# Plan1.net
KiCad netlist of a schematic drawn in EAGLE
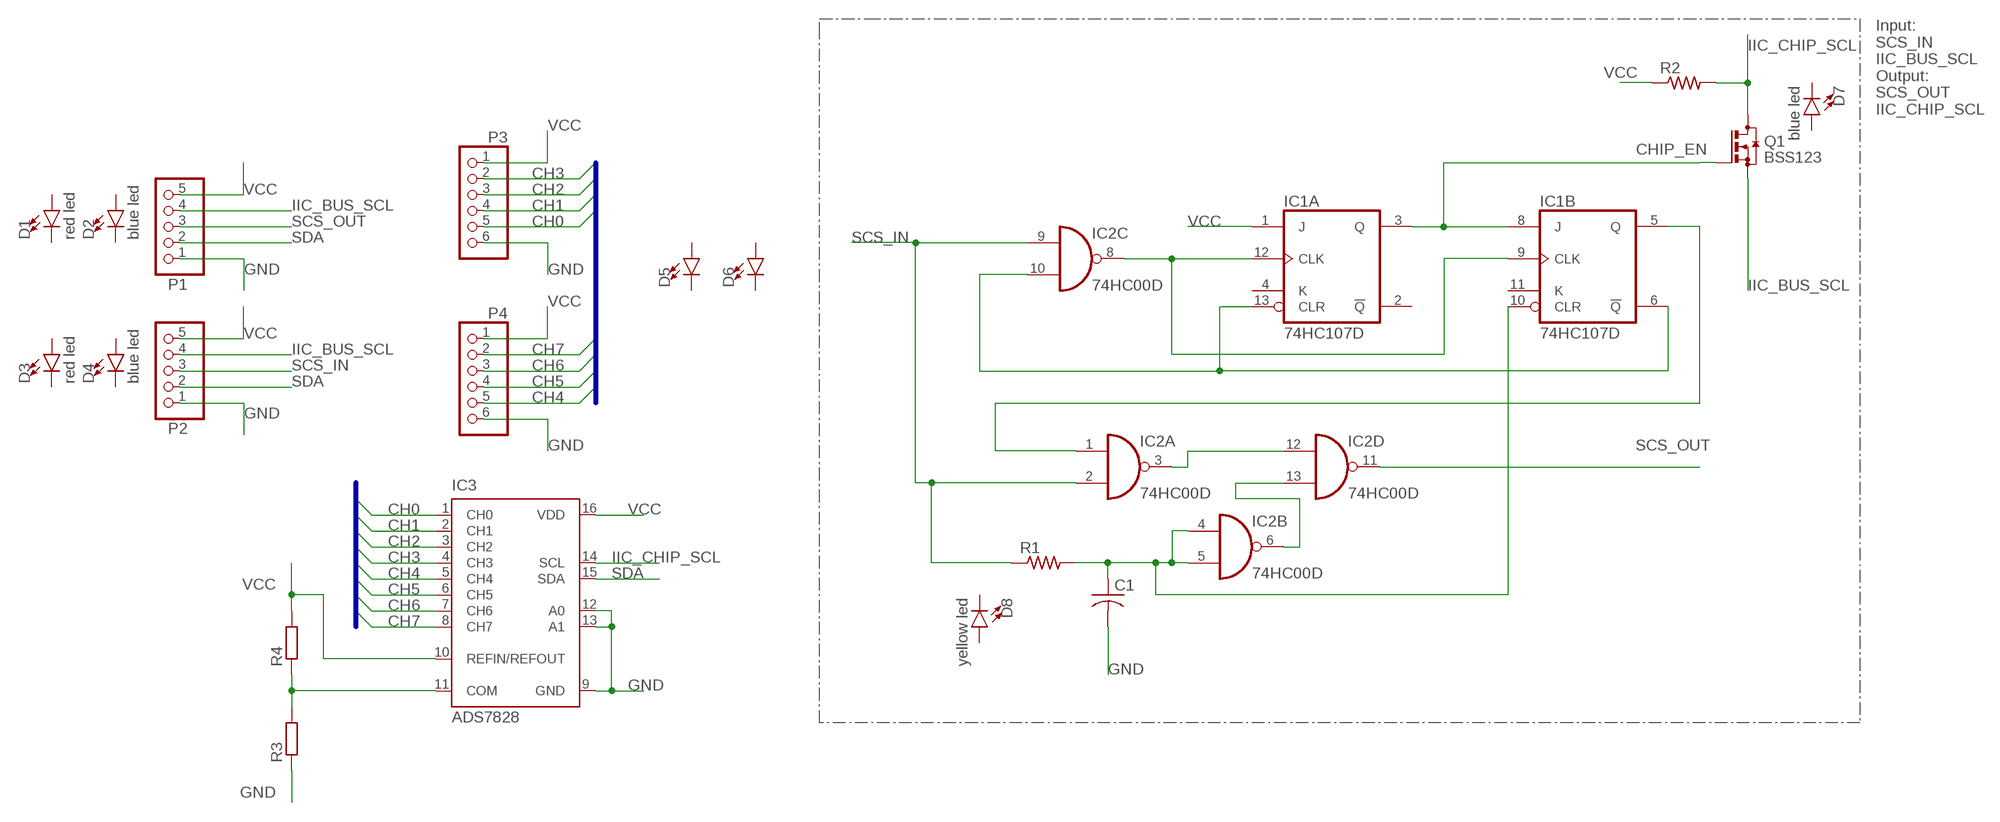
[diagram p0: schematic, sheet 1]

(export (version "E")
  (design (tool "Eeschema 10.0.6"))
  (components
    (comp (ref "C1")
      (value "C-USC1206")
      (footprint "eagle-import:C1206")
      (libsource (lib "eagle-import") (part "C-USC1206"))
    )
    (comp (ref "D1")
      (value "red led")
      (footprint "eagle-import:LED-0603")
      (libsource (lib "eagle-import") (part "LED0603"))
    )
    (comp (ref "D2")
      (value "blue led")
      (footprint "eagle-import:LED-0603")
      (libsource (lib "eagle-import") (part "LED0603"))
    )
    (comp (ref "D3")
      (value "red led")
      (footprint "eagle-import:LED-0603")
      (libsource (lib "eagle-import") (part "LED0603"))
    )
    (comp (ref "D4")
      (value "blue led")
      (footprint "eagle-import:LED-0603")
      (libsource (lib "eagle-import") (part "LED0603"))
    )
    (comp (ref "D5")
      (value "LED0603")
      (footprint "eagle-import:LED-0603")
      (libsource (lib "eagle-import") (part "LED0603"))
    )
    (comp (ref "D6")
      (value "LED0603")
      (footprint "eagle-import:LED-0603")
      (libsource (lib "eagle-import") (part "LED0603"))
    )
    (comp (ref "D7")
      (value "blue led")
      (footprint "eagle-import:LED-0603")
      (libsource (lib "eagle-import") (part "LED0603"))
    )
    (comp (ref "D8")
      (value "yellow led")
      (footprint "eagle-import:LED-0603")
      (libsource (lib "eagle-import") (part "LED0603"))
    )
    (comp (ref "IC1")
      (value "74HC107D")
      (footprint "eagle-import:SO14")
      (libsource (lib "eagle-import") (part "74107DHC"))
    )
    (comp (ref "IC2")
      (value "74HC00D")
      (footprint "eagle-import:SO14")
      (libsource (lib "eagle-import") (part "7400DHC"))
    )
    (comp (ref "IC3")
      (value "ADS7828")
      (footprint "eagle-import:TSSOP16-PW")
      (fields (field (name "MF") "TEXAS INSTRUMENTS") (field (name "MPN") "ADS7828E/250"))
      (libsource (lib "eagle-import") (part "ADS7828"))
    )
    (comp (ref "P1")
      (value "105313-05")
      (footprint "eagle-import:105313-__05")
      (fields (field (name "MF") "Molex"))
      (libsource (lib "eagle-import") (part "105313-05"))
    )
    (comp (ref "P2")
      (value "105313-05")
      (footprint "eagle-import:105313-__05")
      (fields (field (name "MF") "Molex"))
      (libsource (lib "eagle-import") (part "105313-05"))
    )
    (comp (ref "P3")
      (value "105313-06")
      (footprint "eagle-import:105313-__06")
      (fields (field (name "MF") "Molex"))
      (libsource (lib "eagle-import") (part "105313-06"))
    )
    (comp (ref "P4")
      (value "105313-06")
      (footprint "eagle-import:105313-__06")
      (fields (field (name "MF") "Molex"))
      (libsource (lib "eagle-import") (part "105313-06"))
    )
    (comp (ref "Q1")
      (value "BSS123")
      (footprint "eagle-import:SOT23")
      (libsource (lib "eagle-import") (part "BSS123"))
    )
    (comp (ref "R1")
      (value "R-US_R1206")
      (footprint "eagle-import:R1206")
      (libsource (lib "eagle-import") (part "R-US_R1206"))
    )
    (comp (ref "R2")
      (value "R-US_R1206")
      (footprint "eagle-import:R1206")
      (libsource (lib "eagle-import") (part "R-US_R1206"))
    )
    (comp (ref "R3")
      (value "R-EU_R2012")
      (footprint "eagle-import:R2012")
      (libsource (lib "eagle-import") (part "R-EU_R2012"))
    )
    (comp (ref "R4")
      (value "R-EU_R2012")
      (footprint "eagle-import:R2012")
      (libsource (lib "eagle-import") (part "R-EU_R2012"))
    )
  )
  (nets
    (net (code "10") (name "CH0") (class "Default")
      (node (ref "IC3") (pin "1") (pinfunction "CH0_1") (pintype "input"))
      (node (ref "P3") (pin "5") (pinfunction "5_5") (pintype "passive"))
    )
    (net (code "11") (name "CH1") (class "Default")
      (node (ref "IC3") (pin "2") (pinfunction "CH1_2") (pintype "input"))
      (node (ref "P3") (pin "4") (pinfunction "4_4") (pintype "passive"))
    )
    (net (code "12") (name "CH2") (class "Default")
      (node (ref "IC3") (pin "3") (pinfunction "CH2_3") (pintype "input"))
      (node (ref "P3") (pin "3") (pinfunction "3_3") (pintype "passive"))
    )
    (net (code "13") (name "CH3") (class "Default")
      (node (ref "IC3") (pin "4") (pinfunction "CH3_4") (pintype "input"))
      (node (ref "P3") (pin "2") (pinfunction "2_2") (pintype "passive"))
    )
    (net (code "14") (name "CH4") (class "Default")
      (node (ref "IC3") (pin "5") (pinfunction "CH4_5") (pintype "input"))
      (node (ref "P4") (pin "5") (pinfunction "5_5") (pintype "passive"))
    )
    (net (code "15") (name "CH5") (class "Default")
      (node (ref "IC3") (pin "6") (pinfunction "CH5_6") (pintype "input"))
      (node (ref "P4") (pin "4") (pinfunction "4_4") (pintype "passive"))
    )
    (net (code "16") (name "CH6") (class "Default")
      (node (ref "IC3") (pin "7") (pinfunction "CH6_7") (pintype "input"))
      (node (ref "P4") (pin "3") (pinfunction "3_3") (pintype "passive"))
    )
    (net (code "17") (name "CH7") (class "Default")
      (node (ref "IC3") (pin "8") (pinfunction "CH7_8") (pintype "input"))
      (node (ref "P4") (pin "2") (pinfunction "2_2") (pintype "passive"))
    )
    (net (code "18") (name "CHIP_EN") (class "Default")
      (node (ref "IC1") (pin "3") (pinfunction "Q_3") (pintype "output"))
      (node (ref "IC1") (pin "8") (pinfunction "J_8") (pintype "input"))
      (node (ref "Q1") (pin "1") (pinfunction "G_1") (pintype "passive"))
    )
    (net (code "19") (name "GND") (class "Default")
      (node (ref "C1") (pin "2") (pinfunction "2_2") (pintype "passive"))
      (node (ref "IC3") (pin "12") (pinfunction "A0_12") (pintype "input"))
      (node (ref "IC3") (pin "13") (pinfunction "A1_13") (pintype "input"))
      (node (ref "IC3") (pin "9") (pinfunction "GND_9") (pintype "power_in"))
      (node (ref "P1") (pin "1") (pinfunction "1_1") (pintype "passive"))
      (node (ref "P2") (pin "1") (pinfunction "1_1") (pintype "passive"))
      (node (ref "P3") (pin "6") (pinfunction "6_6") (pintype "passive"))
      (node (ref "P4") (pin "6") (pinfunction "6_6") (pintype "passive"))
      (node (ref "R3") (pin "1") (pinfunction "1_1") (pintype "passive"))
    )
    (net (code "20") (name "IIC_BUS_SCL") (class "Default")
      (node (ref "P1") (pin "4") (pinfunction "4_4") (pintype "passive"))
      (node (ref "P2") (pin "4") (pinfunction "4_4") (pintype "passive"))
      (node (ref "Q1") (pin "2") (pinfunction "S_2") (pintype "passive"))
    )
    (net (code "21") (name "IIC_CHIP_SCL") (class "Default")
      (node (ref "IC3") (pin "14") (pinfunction "SCL_14") (pintype "input"))
      (node (ref "Q1") (pin "3") (pinfunction "D_3") (pintype "passive"))
      (node (ref "R2") (pin "2") (pinfunction "2_2") (pintype "passive"))
    )
    (net (code "22") (name "Net-(IC1A-CLK)") (class "Default")
      (node (ref "IC1") (pin "12") (pinfunction "CLK_12") (pintype "input"))
      (node (ref "IC1") (pin "9") (pinfunction "CLK_9") (pintype "input"))
      (node (ref "IC2") (pin "8") (pinfunction "O_8") (pintype "output"))
    )
    (net (code "23") (name "Net-(IC1A-CLR)") (class "Default")
      (node (ref "IC1") (pin "13") (pinfunction "CLR_13") (pintype "input"))
      (node (ref "IC1") (pin "6") (pinfunction "~{Q}_6") (pintype "output"))
      (node (ref "IC2") (pin "10") (pinfunction "I1_10") (pintype "input"))
    )
    (net (code "24") (name "Net-(IC1B-CLR)") (class "Default")
      (node (ref "C1") (pin "1") (pinfunction "1_1") (pintype "passive"))
      (node (ref "IC1") (pin "10") (pinfunction "CLR_10") (pintype "input"))
      (node (ref "IC2") (pin "4") (pinfunction "I0_4") (pintype "input"))
      (node (ref "IC2") (pin "5") (pinfunction "I1_5") (pintype "input"))
      (node (ref "R1") (pin "2") (pinfunction "2_2") (pintype "passive"))
    )
    (net (code "25") (name "Net-(IC1B-Q)") (class "Default")
      (node (ref "IC1") (pin "5") (pinfunction "Q_5") (pintype "output"))
      (node (ref "IC2") (pin "1") (pinfunction "I0_1") (pintype "input"))
    )
    (net (code "26") (name "Net-(IC2A-O)") (class "Default")
      (node (ref "IC2") (pin "12") (pinfunction "I0_12") (pintype "input"))
      (node (ref "IC2") (pin "3") (pinfunction "O_3") (pintype "output"))
    )
    (net (code "27") (name "Net-(IC2B-O)") (class "Default")
      (node (ref "IC2") (pin "13") (pinfunction "I1_13") (pintype "input"))
      (node (ref "IC2") (pin "6") (pinfunction "O_6") (pintype "output"))
    )
    (net (code "28") (name "Net-(IC3-COM)") (class "Default")
      (node (ref "IC3") (pin "11") (pinfunction "COM_11") (pintype "input"))
      (node (ref "R3") (pin "2") (pinfunction "2_2") (pintype "passive"))
      (node (ref "R4") (pin "1") (pinfunction "1_1") (pintype "passive"))
    )
    (net (code "29") (name "SCS_IN") (class "Default")
      (node (ref "IC2") (pin "2") (pinfunction "I1_2") (pintype "input"))
      (node (ref "IC2") (pin "9") (pinfunction "I0_9") (pintype "input"))
      (node (ref "P2") (pin "3") (pinfunction "3_3") (pintype "passive"))
      (node (ref "R1") (pin "1") (pinfunction "1_1") (pintype "passive"))
    )
    (net (code "30") (name "SCS_OUT") (class "Default")
      (node (ref "IC2") (pin "11") (pinfunction "O_11") (pintype "output"))
      (node (ref "P1") (pin "3") (pinfunction "3_3") (pintype "passive"))
    )
    (net (code "31") (name "SDA") (class "Default")
      (node (ref "IC3") (pin "15") (pinfunction "SDA_15") (pintype "bidirectional"))
      (node (ref "P1") (pin "2") (pinfunction "2_2") (pintype "passive"))
      (node (ref "P2") (pin "2") (pinfunction "2_2") (pintype "passive"))
    )
    (net (code "32") (name "VCC") (class "Default")
      (node (ref "IC1") (pin "1") (pinfunction "J_1") (pintype "input"))
      (node (ref "IC3") (pin "10") (pinfunction "REFIN/REFOUT_10") (pintype "passive"))
      (node (ref "IC3") (pin "16") (pinfunction "VDD_16") (pintype "power_in"))
      (node (ref "P1") (pin "5") (pinfunction "5_5") (pintype "passive"))
      (node (ref "P2") (pin "5") (pinfunction "5_5") (pintype "passive"))
      (node (ref "P3") (pin "1") (pinfunction "1_1") (pintype "passive"))
      (node (ref "P4") (pin "1") (pinfunction "1_1") (pintype "passive"))
      (node (ref "R2") (pin "1") (pinfunction "1_1") (pintype "passive"))
      (node (ref "R4") (pin "2") (pinfunction "2_2") (pintype "passive"))
    )
    (net (code "33") (name "unconnected-(D1-PadA)") (class "Default")
      (node (ref "D1") (pin "A") (pinfunction "A_A") (pintype "passive"))
    )
    (net (code "34") (name "unconnected-(D1-PadC)") (class "Default")
      (node (ref "D1") (pin "C") (pinfunction "C_C") (pintype "passive"))
    )
    (net (code "35") (name "unconnected-(D2-PadA)") (class "Default")
      (node (ref "D2") (pin "A") (pinfunction "A_A") (pintype "passive"))
    )
    (net (code "36") (name "unconnected-(D2-PadC)") (class "Default")
      (node (ref "D2") (pin "C") (pinfunction "C_C") (pintype "passive"))
    )
    (net (code "37") (name "unconnected-(D3-PadA)") (class "Default")
      (node (ref "D3") (pin "A") (pinfunction "A_A") (pintype "passive"))
    )
    (net (code "38") (name "unconnected-(D3-PadC)") (class "Default")
      (node (ref "D3") (pin "C") (pinfunction "C_C") (pintype "passive"))
    )
    (net (code "39") (name "unconnected-(D4-PadA)") (class "Default")
      (node (ref "D4") (pin "A") (pinfunction "A_A") (pintype "passive"))
    )
    (net (code "40") (name "unconnected-(D4-PadC)") (class "Default")
      (node (ref "D4") (pin "C") (pinfunction "C_C") (pintype "passive"))
    )
    (net (code "41") (name "unconnected-(D5-PadA)") (class "Default")
      (node (ref "D5") (pin "A") (pinfunction "A_A") (pintype "passive"))
    )
    (net (code "42") (name "unconnected-(D5-PadC)") (class "Default")
      (node (ref "D5") (pin "C") (pinfunction "C_C") (pintype "passive"))
    )
    (net (code "43") (name "unconnected-(D6-PadA)") (class "Default")
      (node (ref "D6") (pin "A") (pinfunction "A_A") (pintype "passive"))
    )
    (net (code "44") (name "unconnected-(D6-PadC)") (class "Default")
      (node (ref "D6") (pin "C") (pinfunction "C_C") (pintype "passive"))
    )
    (net (code "45") (name "unconnected-(D7-PadA)") (class "Default")
      (node (ref "D7") (pin "A") (pinfunction "A_A") (pintype "passive"))
    )
    (net (code "46") (name "unconnected-(D7-PadC)") (class "Default")
      (node (ref "D7") (pin "C") (pinfunction "C_C") (pintype "passive"))
    )
    (net (code "47") (name "unconnected-(D8-PadA)") (class "Default")
      (node (ref "D8") (pin "A") (pinfunction "A_A") (pintype "passive"))
    )
    (net (code "48") (name "unconnected-(D8-PadC)") (class "Default")
      (node (ref "D8") (pin "C") (pinfunction "C_C") (pintype "passive"))
    )
    (net (code "49") (name "unconnected-(IC1A-K-Pad4)") (class "Default")
      (node (ref "IC1") (pin "4") (pinfunction "K_4") (pintype "input"))
    )
    (net (code "50") (name "unconnected-(IC1A-~{Q}-Pad2)") (class "Default")
      (node (ref "IC1") (pin "2") (pinfunction "~{Q}_2") (pintype "output"))
    )
    (net (code "51") (name "unconnected-(IC1B-K-Pad11)") (class "Default")
      (node (ref "IC1") (pin "11") (pinfunction "K_11") (pintype "input"))
    )
  )
)
